# IronDoorControl.net
KiCad netlist of a schematic drawn in Altium Designer
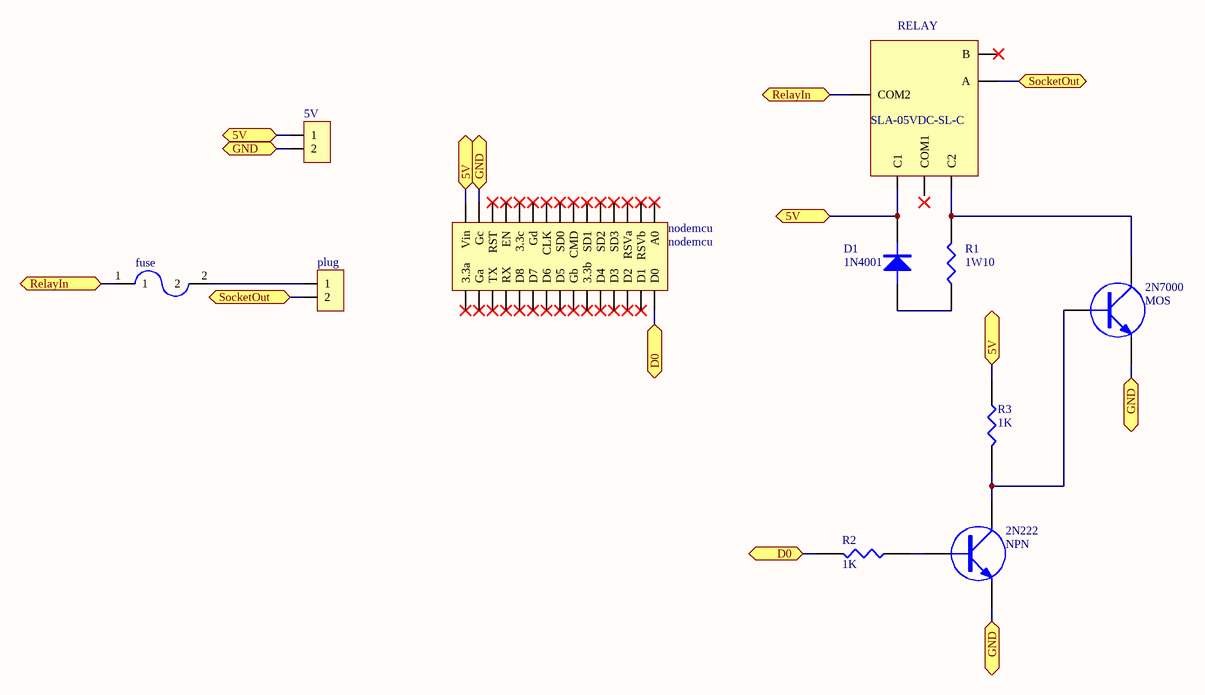
[diagram p0: IronDoorControl.SchDoc]

(export (version "E")
  (design (tool "Eeschema 10.0.6"))
  (components
    (comp (ref "2N222")
      (value "NPN")
      (footprint "TO92-MPS2222A")
      (description "NPN Transistor")
      (libsource (lib "Miscellaneous Devices") (part "NPN"))
    )
    (comp (ref "2N7000")
      (value "MOS")
      (footprint "TO92-MPS2222A")
      (description "NPN Transistor")
      (libsource (lib "Miscellaneous Devices") (part "NPN"))
    )
    (comp (ref "5V")
      (value "BigGreenMos")
      (footprint "BigGreenMos")
      (libsource (lib "BigGreenMos") (part "BigGreenMos"))
    )
    (comp (ref "D1")
      (value "1N4001")
      (footprint "DIODE8mm")
      (description "Diode")
      (libsource (lib "DIODE_SCH") (part "DIODE"))
    )
    (comp (ref "fuse")
      (value "FUSE20mm")
      (footprint "FUSE20mm")
      (libsource (lib "FUSE20mm") (part "FUSE20mm"))
    )
    (comp (ref "nodemcu")
      (value "nodemcu")
      (footprint "nodemcu")
      (libsource (lib "nodemcu") (part "nodemcu"))
    )
    (comp (ref "plug")
      (value "BigGreenMos")
      (footprint "BigGreenMos")
      (libsource (lib "BigGreenMos") (part "BigGreenMos"))
    )
    (comp (ref "R1")
      (value "1W10")
      (footprint "RES0.6")
      (libsource (lib "Miscellaneous Devices") (part "RES1"))
    )
    (comp (ref "R2")
      (value "1K")
      (footprint "RES0.4")
      (libsource (lib "Miscellaneous Devices") (part "RES1"))
    )
    (comp (ref "R3")
      (value "1K")
      (footprint "RES0.4")
      (libsource (lib "Miscellaneous Devices") (part "RES1"))
    )
    (comp (ref "RELAY")
      (value "SLA-05VDC-SL-C")
      (footprint "SLA-05VDC-SL-C")
      (libsource (lib "SLA-05VDC-SL-C") (part "SLA-05VDC-SL-C"))
    )
  )
  (nets
    (net (code "1") (name "/5V") (class "Default")
      (node (ref "5V") (pin "1") (pinfunction "1_1") (pintype "passive"))
      (node (ref "D1") (pin "N") (pinfunction "N_N") (pintype "passive"))
      (node (ref "R3") (pin "1") (pinfunction "1_1") (pintype "passive"))
      (node (ref "RELAY") (pin "C1") (pinfunction "C1_C1") (pintype "passive"))
      (node (ref "nodemcu") (pin "Vin") (pinfunction "Vin_Vin") (pintype "passive"))
    )
    (net (code "2") (name "/D0") (class "Default")
      (node (ref "R2") (pin "2") (pinfunction "2_2") (pintype "passive"))
      (node (ref "nodemcu") (pin "D0") (pinfunction "D0_D0") (pintype "passive"))
    )
    (net (code "3") (name "/GND") (class "Default")
      (node (ref "2N222") (pin "3") (pinfunction "E_3") (pintype "passive"))
      (node (ref "2N7000") (pin "3") (pinfunction "E_3") (pintype "passive"))
      (node (ref "5V") (pin "2") (pinfunction "2_2") (pintype "passive"))
      (node (ref "nodemcu") (pin "Gc") (pinfunction "Gc_Gc") (pintype "passive"))
    )
    (net (code "4") (name "/RelayIn") (class "Default")
      (node (ref "RELAY") (pin "COM2") (pinfunction "COM2_COM2") (pintype "passive"))
      (node (ref "fuse") (pin "1") (pinfunction "1_1") (pintype "passive"))
    )
    (net (code "5") (name "/SocketOut") (class "Default")
      (node (ref "RELAY") (pin "A") (pinfunction "A_A") (pintype "passive"))
      (node (ref "plug") (pin "2") (pinfunction "2_2") (pintype "passive"))
    )
    (net (code "6") (name "Net-(2N222-B)") (class "Default")
      (node (ref "2N222") (pin "1") (pinfunction "B_1") (pintype "passive"))
      (node (ref "R2") (pin "1") (pinfunction "1_1") (pintype "passive"))
    )
    (net (code "7") (name "Net-(2N222-C)") (class "Default")
      (node (ref "2N222") (pin "2") (pinfunction "C_2") (pintype "passive"))
      (node (ref "2N7000") (pin "1") (pinfunction "B_1") (pintype "passive"))
      (node (ref "R3") (pin "2") (pinfunction "2_2") (pintype "passive"))
    )
    (net (code "8") (name "Net-(2N7000-C)") (class "Default")
      (node (ref "2N7000") (pin "2") (pinfunction "C_2") (pintype "passive"))
      (node (ref "R1") (pin "2") (pinfunction "2_2") (pintype "passive"))
      (node (ref "RELAY") (pin "C2") (pinfunction "C2_C2") (pintype "passive"))
    )
    (net (code "9") (name "Net-(D1-PadP)") (class "Default")
      (node (ref "D1") (pin "P") (pinfunction "P_P") (pintype "passive"))
      (node (ref "R1") (pin "1") (pinfunction "1_1") (pintype "passive"))
    )
    (net (code "10") (name "Net-(fuse-Pad2)") (class "Default")
      (node (ref "fuse") (pin "2") (pinfunction "2_2") (pintype "passive"))
      (node (ref "plug") (pin "1") (pinfunction "1_1") (pintype "passive"))
    )
    (net (code "11") (name "unconnected-(RELAY-PadB)") (class "Default")
      (node (ref "RELAY") (pin "B") (pinfunction "B_B") (pintype "passive+no_connect"))
    )
    (net (code "12") (name "unconnected-(RELAY-PadCOM1)") (class "Default")
      (node (ref "RELAY") (pin "COM1") (pinfunction "COM1_COM1") (pintype "passive"))
    )
    (net (code "13") (name "unconnected-(nodemcu-Pad3.3a)") (class "Default")
      (node (ref "nodemcu") (pin "3.3a") (pinfunction "3.3a_3.3a") (pintype "passive+no_connect"))
    )
    (net (code "14") (name "unconnected-(nodemcu-Pad3.3b)") (class "Default")
      (node (ref "nodemcu") (pin "3.3b") (pinfunction "3.3b_3.3b") (pintype "passive+no_connect"))
    )
    (net (code "15") (name "unconnected-(nodemcu-Pad3.3c)") (class "Default")
      (node (ref "nodemcu") (pin "3.3c") (pinfunction "3.3c_3.3c") (pintype "passive+no_connect"))
    )
    (net (code "16") (name "unconnected-(nodemcu-PadA0)") (class "Default")
      (node (ref "nodemcu") (pin "A0") (pinfunction "A0_A0") (pintype "passive+no_connect"))
    )
    (net (code "17") (name "unconnected-(nodemcu-PadCLK)") (class "Default")
      (node (ref "nodemcu") (pin "CLK") (pinfunction "CLK_CLK") (pintype "passive+no_connect"))
    )
    (net (code "18") (name "unconnected-(nodemcu-PadCMD)") (class "Default")
      (node (ref "nodemcu") (pin "CMD") (pinfunction "CMD_CMD") (pintype "passive+no_connect"))
    )
    (net (code "19") (name "unconnected-(nodemcu-PadD1)") (class "Default")
      (node (ref "nodemcu") (pin "D1") (pinfunction "D1_D1") (pintype "passive+no_connect"))
    )
    (net (code "20") (name "unconnected-(nodemcu-PadD2)") (class "Default")
      (node (ref "nodemcu") (pin "D2") (pinfunction "D2_D2") (pintype "passive+no_connect"))
    )
    (net (code "21") (name "unconnected-(nodemcu-PadD3)") (class "Default")
      (node (ref "nodemcu") (pin "D3") (pinfunction "D3_D3") (pintype "passive+no_connect"))
    )
    (net (code "22") (name "unconnected-(nodemcu-PadD4)") (class "Default")
      (node (ref "nodemcu") (pin "D4") (pinfunction "D4_D4") (pintype "passive+no_connect"))
    )
    (net (code "23") (name "unconnected-(nodemcu-PadD5)") (class "Default")
      (node (ref "nodemcu") (pin "D5") (pinfunction "D5_D5") (pintype "passive+no_connect"))
    )
    (net (code "24") (name "unconnected-(nodemcu-PadD6)") (class "Default")
      (node (ref "nodemcu") (pin "D6") (pinfunction "D6_D6") (pintype "passive+no_connect"))
    )
    (net (code "25") (name "unconnected-(nodemcu-PadD7)") (class "Default")
      (node (ref "nodemcu") (pin "D7") (pinfunction "D7_D7") (pintype "passive+no_connect"))
    )
    (net (code "26") (name "unconnected-(nodemcu-PadD8)") (class "Default")
      (node (ref "nodemcu") (pin "D8") (pinfunction "D8_D8") (pintype "passive+no_connect"))
    )
    (net (code "27") (name "unconnected-(nodemcu-PadEN)") (class "Default")
      (node (ref "nodemcu") (pin "EN") (pinfunction "EN_EN") (pintype "passive+no_connect"))
    )
    (net (code "28") (name "unconnected-(nodemcu-PadGa)") (class "Default")
      (node (ref "nodemcu") (pin "Ga") (pinfunction "Ga_Ga") (pintype "passive+no_connect"))
    )
    (net (code "29") (name "unconnected-(nodemcu-PadGb)") (class "Default")
      (node (ref "nodemcu") (pin "Gb") (pinfunction "Gb_Gb") (pintype "passive+no_connect"))
    )
    (net (code "30") (name "unconnected-(nodemcu-PadGd)") (class "Default")
      (node (ref "nodemcu") (pin "Gd") (pinfunction "Gd_Gd") (pintype "passive+no_connect"))
    )
    (net (code "31") (name "unconnected-(nodemcu-PadRST)") (class "Default")
      (node (ref "nodemcu") (pin "RST") (pinfunction "RST_RST") (pintype "passive+no_connect"))
    )
    (net (code "32") (name "unconnected-(nodemcu-PadRSVb)") (class "Default")
      (node (ref "nodemcu") (pin "RSVb") (pinfunction "RSVb_RSVb") (pintype "passive+no_connect"))
    )
    (net (code "33") (name "unconnected-(nodemcu-PadRX)") (class "Default")
      (node (ref "nodemcu") (pin "RX") (pinfunction "RX_RX") (pintype "passive+no_connect"))
    )
    (net (code "34") (name "unconnected-(nodemcu-PadSD0)") (class "Default")
      (node (ref "nodemcu") (pin "SD0") (pinfunction "SD0_SD0") (pintype "passive+no_connect"))
    )
    (net (code "35") (name "unconnected-(nodemcu-PadSD1)") (class "Default")
      (node (ref "nodemcu") (pin "SD1") (pinfunction "SD1_SD1") (pintype "passive+no_connect"))
    )
    (net (code "36") (name "unconnected-(nodemcu-PadSD2)") (class "Default")
      (node (ref "nodemcu") (pin "SD2") (pinfunction "SD2_SD2") (pintype "passive+no_connect"))
    )
    (net (code "37") (name "unconnected-(nodemcu-PadSD3)") (class "Default")
      (node (ref "nodemcu") (pin "SD3") (pinfunction "SD3_SD3") (pintype "passive+no_connect"))
    )
    (net (code "38") (name "unconnected-(nodemcu-PadTX)") (class "Default")
      (node (ref "nodemcu") (pin "TX") (pinfunction "TX_TX") (pintype "passive+no_connect"))
    )
    (net (code "39") (name "unconnected-(nodemcu-RSVa-PadRSVb)") (class "Default")
      (node (ref "nodemcu") (pin "RSVb") (pinfunction "RSVa_RSVb") (pintype "passive+no_connect"))
    )
  )
)
